# 04-Power_3v3.net
KiCad netlist of a schematic drawn in Altium Designer
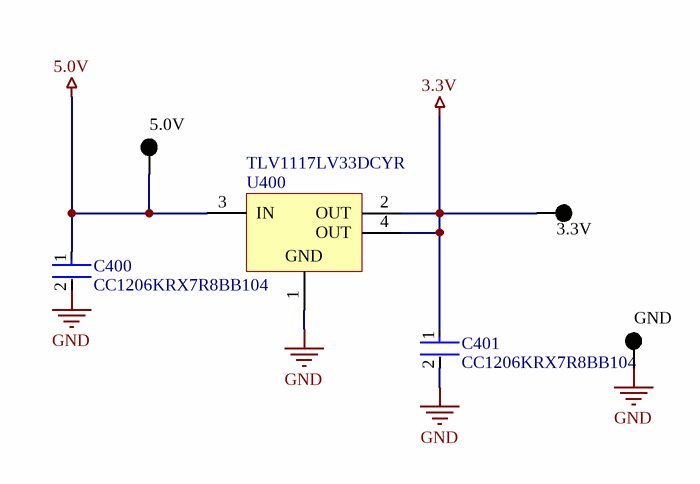
[diagram p0: 04-Power_3v3.SchDoc]

(export (version "E")
  (design (tool "Eeschema 10.0.6"))
  (components
    (comp (ref "3.3V")
      (value "5011")
      (footprint "KSTN-5011_V")
      (description "Test Point, Black, Through Hole, RoHS, Bulk")
      (fields (field (name "MANUFACTURER") "Keystone"))
      (libsource (lib "Altium Content Vault") (part "TESTPOINT_BLACK"))
    )
    (comp (ref "5.0V")
      (value "5011")
      (footprint "KSTN-5011_V")
      (description "Test Point, Black, Through Hole, RoHS, Bulk")
      (fields (field (name "MANUFACTURER") "Keystone"))
      (libsource (lib "Altium Content Vault") (part "TESTPOINT_BLACK"))
    )
    (comp (ref "C400")
      (value "CC1206KRX7R8BB104")
      (footprint "FP-CC1206-1_25-MFG")
      (description "CAP CER 0.1UF 25V X7R 1206")
      (fields
        (field (name "TOLERANCE") "0.1")
        (field (name "OCTOPART") "https://octopart.com/cc1206krx7r8bb104-yageo-42334534")
      )
      (libsource (lib "Altium Content Vault") (part "11868f565c42a9108669ba33697ecf6"))
    )
    (comp (ref "C401")
      (value "CC1206KRX7R8BB104")
      (footprint "FP-CC1206-1_25-MFG")
      (description "CAP CER 0.1UF 25V X7R 1206")
      (fields
        (field (name "TOLERANCE") "0.1")
        (field (name "OCTOPART") "https://octopart.com/cc1206krx7r8bb104-yageo-42334534")
      )
      (libsource (lib "Altium Content Vault") (part "11868f565c42a9108669ba33697ecf6"))
    )
    (comp (ref "GND")
      (value "5011")
      (footprint "KSTN-5011_V")
      (description "Test Point, Black, Through Hole, RoHS, Bulk")
      (fields (field (name "MANUFACTURER") "Keystone"))
      (libsource (lib "Altium Content Vault") (part "TESTPOINT_BLACK"))
    )
    (comp (ref "U400")
      (value "TLV1117LV33DCYR")
      (footprint "DCY0004A_N")
      (fields (field (name "MANUFACTURER") "Texas Instruments"))
      (libsource (lib "Altium Content Vault") (part "TI-TLV1117LV33DCY4"))
    )
  )
  (nets
    (net (code "1") (name "3.3V") (class "Default")
      (node (ref "3.3V") (pin "1") (pinfunction "1_1") (pintype "passive"))
      (node (ref "C401") (pin "1") (pinfunction "1_1") (pintype "passive"))
      (node (ref "U400") (pin "2") (pinfunction "OUT_2") (pintype "power_in"))
      (node (ref "U400") (pin "4") (pinfunction "OUT_4") (pintype "power_in"))
    )
    (net (code "2") (name "5.0V") (class "Default")
      (node (ref "5.0V") (pin "1") (pinfunction "1_1") (pintype "passive"))
      (node (ref "C400") (pin "1") (pinfunction "1_1") (pintype "passive"))
      (node (ref "U400") (pin "3") (pinfunction "IN_3") (pintype "power_in"))
    )
    (net (code "3") (name "GND") (class "Default")
      (node (ref "C400") (pin "2") (pinfunction "2_2") (pintype "passive"))
      (node (ref "C401") (pin "2") (pinfunction "2_2") (pintype "passive"))
      (node (ref "GND") (pin "1") (pinfunction "1_1") (pintype "passive"))
      (node (ref "U400") (pin "1") (pinfunction "GND_1") (pintype "power_in"))
    )
  )
)
